# DB10012_ControlTopLevel.net
KiCad netlist of a schematic drawn in Altium Designer
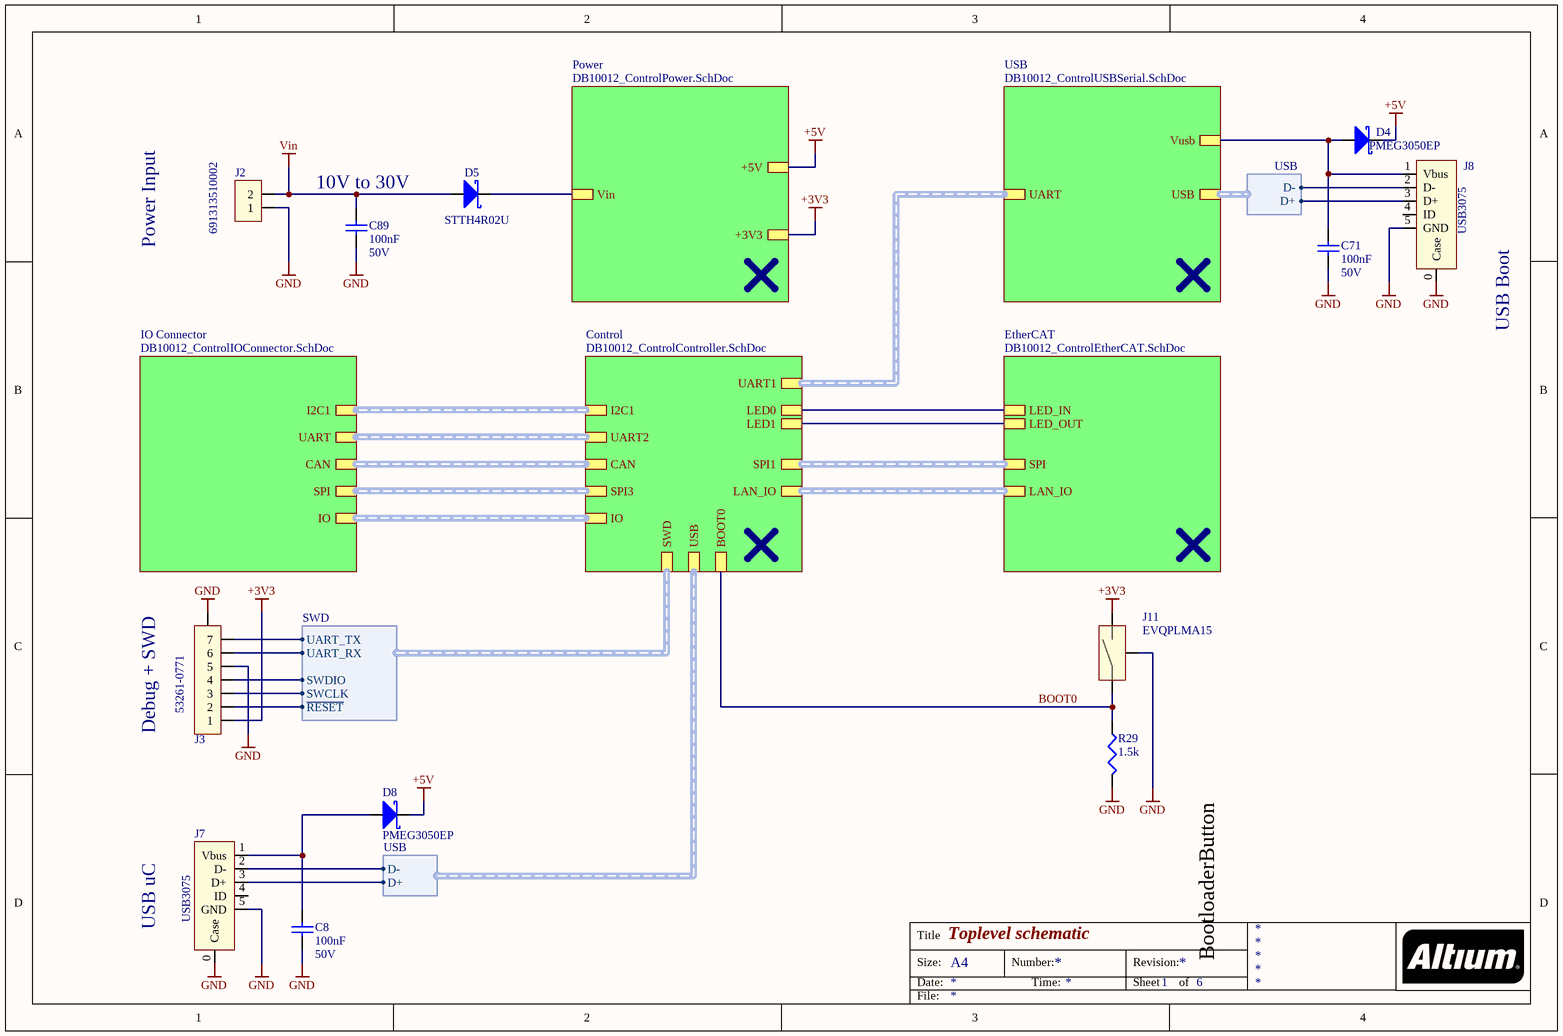
[diagram p0: DB10012_ControlTopLevel.SchDoc]

(export (version "E")
  (design (tool "Eeschema 10.0.6"))
  (components
    (comp (ref "C8")
      (value "100nF")
      (footprint "C-0805")
      (description "Capacitor, 100nF, 50V,  X7R")
      (fields (field (name "VOLTAGE RATING") "50V"))
      (libsource (lib "AR_Capacitors_Ceramic") (part "100nF/0805/CER/50V"))
    )
    (comp (ref "C71")
      (value "100nF")
      (footprint "C-0805")
      (description "Capacitor, 100nF, 50V,  X7R")
      (fields (field (name "VOLTAGE RATING") "50V"))
      (libsource (lib "AR_Capacitors_Ceramic") (part "100nF/0805/CER/50V"))
    )
    (comp (ref "C89")
      (value "100nF")
      (footprint "C-0805")
      (description "Capacitor, 100nF, 50V,  X7R")
      (fields (field (name "VOLTAGE RATING") "50V"))
      (libsource (lib "AR_Capacitors_Ceramic") (part "100nF/0805/CER/50V"))
    )
    (comp (ref "D4")
      (value "PMEG3050EP")
      (footprint "SOD128")
      (description "Diode Schottky, Vrrm: 30V, If: 3A, Vf: 0.36V")
      (libsource (lib "AR_Diodes") (part "PMEG3050EP"))
    )
    (comp (ref "D5")
      (value "STTH4R02U")
      (footprint "CASE 403A-03")
      (description "Diode Schottky, Vrrm: 200V, If: 4A, Vf: 1,05V")
      (libsource (lib "AR_Diodes") (part "STTH4R02U"))
    )
    (comp (ref "D8")
      (value "PMEG3050EP")
      (footprint "SOD128")
      (description "Diode Schottky, Vrrm: 30V, If: 3A, Vf: 0.36V")
      (libsource (lib "AR_Diodes") (part "PMEG3050EP"))
    )
    (comp (ref "J2")
      (value "691313510002")
      (footprint "691313510002")
      (description "WR-TBL 313 Series, 2 Contacts, Header, 5.08 mm")
      (libsource (lib "AR_Connectors") (part "691313510002"))
    )
    (comp (ref "J3")
      (value "53261-0771")
      (footprint "53261-0771")
      (description "PicoBlade 53261 Series, 7Pin, Right Angle")
      (libsource (lib "AR_Connectors") (part "53261-0771"))
    )
    (comp (ref "J7")
      (value "USB3075")
      (footprint "USB3075 - NOSLOT")
      (description "USB 2.0 MICRO B, RCPT, 5POS, SMT")
      (libsource (lib "") (part "USB3075_1"))
    )
    (comp (ref "J8")
      (value "USB3075")
      (footprint "USB3075 - NOSLOT")
      (description "USB 2.0 MICRO B, RCPT, 5POS, SMT")
      (libsource (lib "AR_Connectors") (part "USB3075"))
    )
    (comp (ref "J11")
      (value "EVQPLMA15")
      (footprint "EVQPLM")
      (description "SWITCH, TACT, 4.9MM, SMD, 2.6N")
      (libsource (lib "AR_Misc") (part "EVQPLMA15"))
    )
    (comp (ref "R29")
      (value "1.5k")
      (footprint "0402")
      (description "Resistor, 1.5k, 0.1%, 0.0625W, 50V, 100PPM, 0402")
      (libsource (lib "AR_Resistors_SMD") (part "1.5k/0402/0063W/50V"))
    )
  )
  (nets
    (net (code "3") (name "+3V3") (class "Default")
      (node (ref "J11") (pin "2") (pinfunction "2_2") (pintype "passive"))
      (node (ref "J3") (pin "1") (pinfunction "1_1") (pintype "passive"))
    )
    (net (code "4") (name "+5V") (class "Default")
      (node (ref "D4") (pin "2") (pinfunction "K_2") (pintype "passive"))
      (node (ref "D8") (pin "2") (pinfunction "K_2") (pintype "passive"))
    )
    (net (code "5") (name "/BOOT0") (class "Default")
      (node (ref "J11") (pin "1") (pinfunction "1_1") (pintype "passive"))
      (node (ref "R29") (pin "2") (pinfunction "2_2") (pintype "passive"))
    )
    (net (code "14") (name "/SWCLK") (class "Default")
      (node (ref "J3") (pin "3") (pinfunction "3_3") (pintype "passive"))
    )
    (net (code "15") (name "/SWDIO") (class "Default")
      (node (ref "J3") (pin "4") (pinfunction "4_4") (pintype "passive"))
    )
    (net (code "18") (name "/UART_RX") (class "Default")
      (node (ref "J3") (pin "6") (pinfunction "6_6") (pintype "passive"))
    )
    (net (code "19") (name "/UART_TX") (class "Default")
      (node (ref "J3") (pin "7") (pinfunction "7_7") (pintype "passive"))
    )
    (net (code "20") (name "/Vin") (class "Default")
      (node (ref "D5") (pin "2") (pinfunction "K_2") (pintype "passive"))
    )
    (net (code "21") (name "/Vusb") (class "Default")
      (node (ref "C71") (pin "2") (pinfunction "2_2") (pintype "passive"))
      (node (ref "D4") (pin "1") (pinfunction "A_1") (pintype "passive"))
      (node (ref "J8") (pin "1") (pinfunction "Vbus_1") (pintype "passive"))
    )
    (net (code "24") (name "/~{RESET}") (class "Default")
      (node (ref "J3") (pin "2") (pinfunction "2_2") (pintype "passive"))
    )
    (net (code "25") (name "GND") (class "Default")
      (node (ref "C71") (pin "1") (pinfunction "1_1") (pintype "passive"))
      (node (ref "C8") (pin "1") (pinfunction "1_1") (pintype "passive"))
      (node (ref "C89") (pin "1") (pinfunction "1_1") (pintype "passive"))
      (node (ref "J11") (pin "0") (pinfunction "GND_0") (pintype "passive"))
      (node (ref "J2") (pin "1") (pinfunction "1_1") (pintype "passive"))
      (node (ref "J3") (pin "0") (pinfunction "SHLD_0") (pintype "passive"))
      (node (ref "J3") (pin "5") (pinfunction "5_5") (pintype "passive"))
      (node (ref "J7") (pin "0") (pinfunction "Case_0") (pintype "passive"))
      (node (ref "J7") (pin "5") (pinfunction "GND_5") (pintype "passive"))
      (node (ref "J8") (pin "0") (pinfunction "Case_0") (pintype "passive"))
      (node (ref "J8") (pin "5") (pinfunction "GND_5") (pintype "passive"))
      (node (ref "R29") (pin "1") (pinfunction "1_1") (pintype "passive"))
    )
    (net (code "26") (name "Net-(D8-A)") (class "Default")
      (node (ref "C8") (pin "2") (pinfunction "2_2") (pintype "passive"))
      (node (ref "D8") (pin "1") (pinfunction "A_1") (pintype "passive"))
      (node (ref "J7") (pin "1") (pinfunction "Vbus_1") (pintype "passive"))
    )
    (net (code "27") (name "Vin") (class "Default")
      (node (ref "C89") (pin "2") (pinfunction "2_2") (pintype "passive"))
      (node (ref "D5") (pin "1") (pinfunction "A_1") (pintype "passive"))
      (node (ref "J2") (pin "2") (pinfunction "2_2") (pintype "passive"))
    )
    (net (code "28") (name "unconnected-(J7-D+-Pad3)") (class "Default")
      (node (ref "J7") (pin "3") (pinfunction "D+_3") (pintype "passive"))
    )
    (net (code "29") (name "unconnected-(J7-D--Pad2)") (class "Default")
      (node (ref "J7") (pin "2") (pinfunction "D-_2") (pintype "passive"))
    )
    (net (code "30") (name "unconnected-(J7-ID-Pad4)") (class "Default")
      (node (ref "J7") (pin "4") (pinfunction "ID_4") (pintype "passive"))
    )
    (net (code "31") (name "unconnected-(J8-D+-Pad3)") (class "Default")
      (node (ref "J8") (pin "3") (pinfunction "D+_3") (pintype "passive"))
    )
    (net (code "32") (name "unconnected-(J8-D--Pad2)") (class "Default")
      (node (ref "J8") (pin "2") (pinfunction "D-_2") (pintype "passive"))
    )
    (net (code "33") (name "unconnected-(J8-ID-Pad4)") (class "Default")
      (node (ref "J8") (pin "4") (pinfunction "ID_4") (pintype "passive"))
    )
  )
)
